# IO.net
KiCad netlist of a schematic drawn in Altium Designer
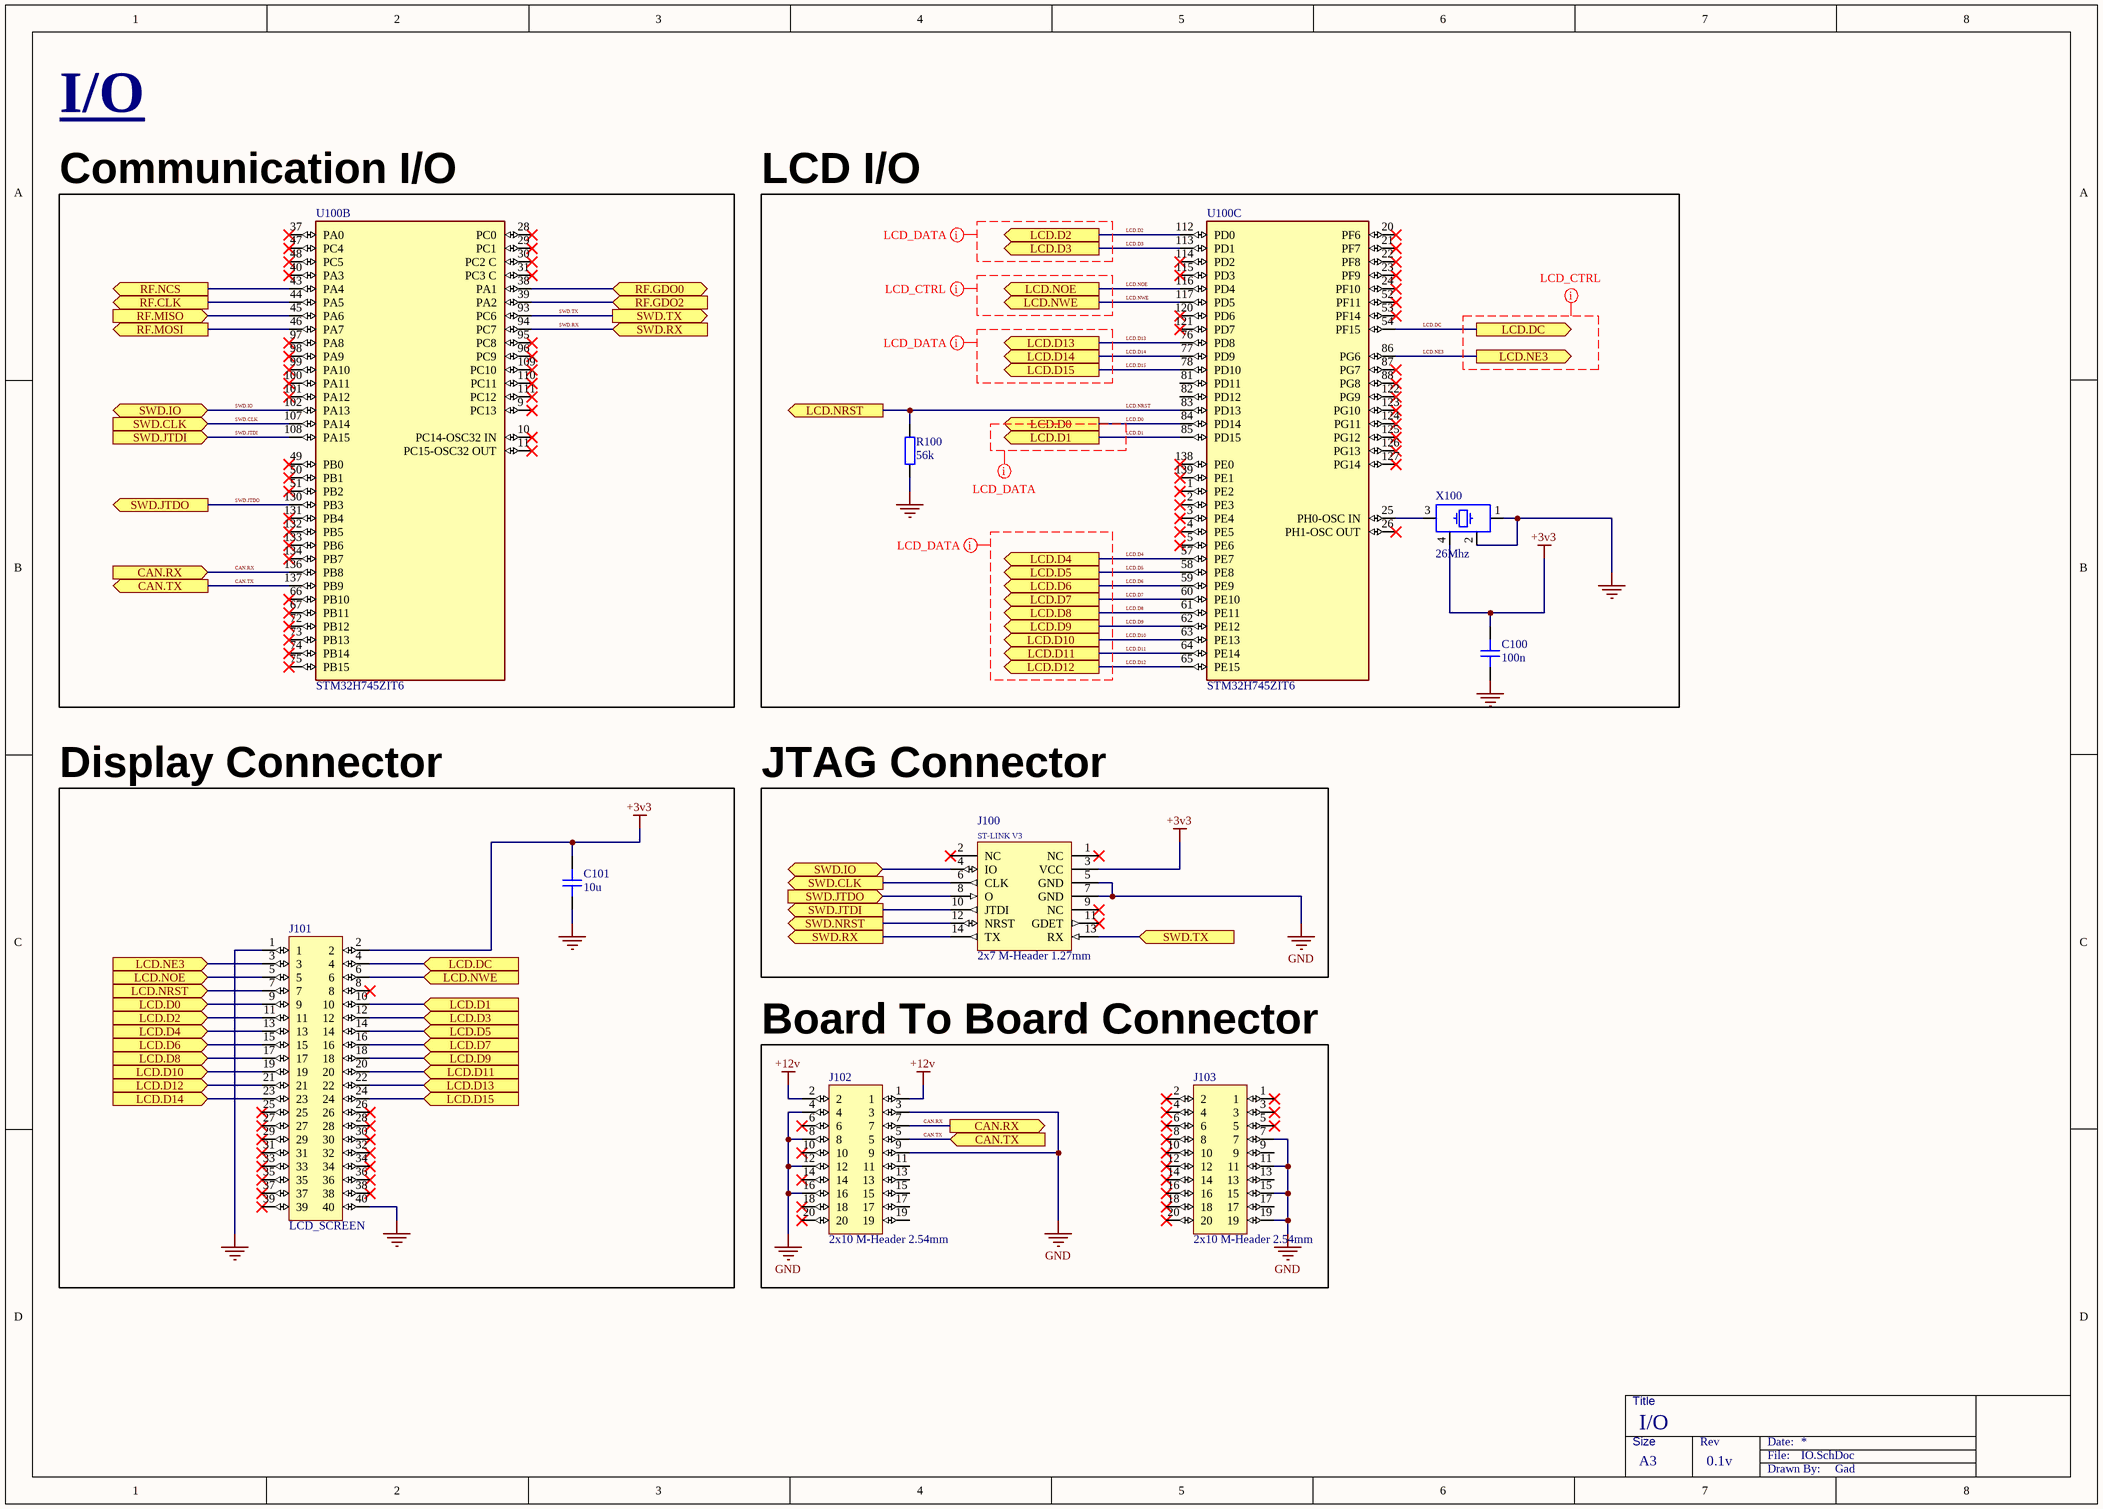
[diagram p0: IO.SchDoc]

(export (version "E")
  (design (tool "Eeschema 10.0.6"))
  (components
    (comp (ref "C100")
      (value "100n")
      (footprint "CAP_0402")
      (description "Capacitor SMD 0402 X7R 50V 10% 100nF")
      (libsource (lib "Schematic-Lib-PhilsLab") (part "CAP_0402"))
    )
    (comp (ref "C101")
      (value "10u")
      (footprint "CAP_0603")
      (description "Capacitor SMD 0603 X5R 25V 10% 10uF")
      (libsource (lib "Schematic-Lib-PhilsLab") (part "CAP_0603"))
    )
    (comp (ref "J100")
      (value "2x7 M-Header 1.27mm")
      (footprint "2x7 M-Header 1.27mm")
      (description "ST-LINK v3-minie Connector")
      (libsource (lib "Schematic-Lib-PhilsLab") (part "2x7 M-Header 1.27mm"))
    )
    (comp (ref "J101")
      (value "LCD_SCREEN")
      (footprint "LCD_Screen")
      (libsource (lib "Schematic-Lib-PhilsLab") (part "LCD_SCREEN"))
    )
    (comp (ref "J102")
      (value "2x10 M-Header 2.54mm")
      (footprint "2x10 M-Header 2.54mm")
      (libsource (lib "") (part "2x10 M-Header 2.54mm_1"))
    )
    (comp (ref "J103")
      (value "2x10 M-Header 2.54mm")
      (footprint "2x10 M-Header 2.54mm")
      (libsource (lib "Schematic-Lib-PhilsLab") (part "2x10 M-Header 2.54mm"))
    )
    (comp (ref "R100")
      (value "56k")
      (footprint "RES_0402")
      (description "Resistor SMD Thick Film 0402 75V 100mW 1% 56kΩ")
      (libsource (lib "Schematic-Lib-PhilsLab") (part "RES_0402"))
    )
    (comp (ref "U100")
      (value "STM32H745ZIT6")
      (footprint "FP-LQFP144-1A-MFG")
      (description "HIGH-PERFORMANCE AND DSP WITH DP")
      (fields
        (field (name "OCTOPART") "https://octopart.com/stm32h745zit6-stmicroelectronics-100293939")
        (field (name "MANUFACTURER") "STMicroelectronics")
      )
      (libsource (lib "Altium Content Vault") (part "f5432ce9894f79c0085309acf87c031"))
    )
    (comp (ref "X100")
      (value "26Mhz")
      (footprint "XTAL_2520")
      (description "Crystal SMD 2520")
      (fields (field (name "MANUFACTURER PART NUMBER") "OW3EL89CENUNFAYLC-26M"))
      (libsource (lib "Schematic-Lib-PhilsLab") (part "XTAL_2520"))
    )
  )
  (nets
    (net (code "1") (name "+3v3") (class "Default")
      (node (ref "C100") (pin "1") (pinfunction "1_1") (pintype "passive"))
      (node (ref "C101") (pin "1") (pinfunction "1_1") (pintype "passive"))
      (node (ref "J100") (pin "3") (pinfunction "VCC_3") (pintype "power_in"))
      (node (ref "J101") (pin "2") (pinfunction "2_2") (pintype "bidirectional"))
      (node (ref "X100") (pin "4") (pinfunction "4_4") (pintype "passive"))
    )
    (net (code "2") (name "+12v") (class "Default")
      (node (ref "J102") (pin "1") (pinfunction "1_1") (pintype "bidirectional"))
      (node (ref "J102") (pin "2") (pinfunction "2_2") (pintype "bidirectional"))
    )
    (net (code "3") (name "/CAN.RX") (class "Default")
      (node (ref "J102") (pin "7") (pinfunction "7_7") (pintype "bidirectional"))
      (node (ref "U100") (pin "136") (pinfunction "PB8_136") (pintype "bidirectional"))
    )
    (net (code "4") (name "/CAN.TX") (class "Default")
      (node (ref "J102") (pin "5") (pinfunction "5_5") (pintype "bidirectional"))
      (node (ref "U100") (pin "137") (pinfunction "PB9_137") (pintype "bidirectional"))
    )
    (net (code "5") (name "/LCD.D0") (class "Default")
      (node (ref "J101") (pin "9") (pinfunction "9_9") (pintype "bidirectional"))
      (node (ref "U100") (pin "84") (pinfunction "PD14_84") (pintype "bidirectional"))
    )
    (net (code "6") (name "/LCD.D1") (class "Default")
      (node (ref "J101") (pin "10") (pinfunction "10_10") (pintype "bidirectional"))
      (node (ref "U100") (pin "85") (pinfunction "PD15_85") (pintype "bidirectional"))
    )
    (net (code "7") (name "/LCD.D2") (class "Default")
      (node (ref "J101") (pin "11") (pinfunction "11_11") (pintype "bidirectional"))
      (node (ref "U100") (pin "112") (pinfunction "PD0_112") (pintype "bidirectional"))
    )
    (net (code "8") (name "/LCD.D3") (class "Default")
      (node (ref "J101") (pin "12") (pinfunction "12_12") (pintype "bidirectional"))
      (node (ref "U100") (pin "113") (pinfunction "PD1_113") (pintype "bidirectional"))
    )
    (net (code "9") (name "/LCD.D4") (class "Default")
      (node (ref "J101") (pin "13") (pinfunction "13_13") (pintype "bidirectional"))
      (node (ref "U100") (pin "57") (pinfunction "PE7_57") (pintype "bidirectional"))
    )
    (net (code "10") (name "/LCD.D5") (class "Default")
      (node (ref "J101") (pin "14") (pinfunction "14_14") (pintype "bidirectional"))
      (node (ref "U100") (pin "58") (pinfunction "PE8_58") (pintype "bidirectional"))
    )
    (net (code "11") (name "/LCD.D6") (class "Default")
      (node (ref "J101") (pin "15") (pinfunction "15_15") (pintype "bidirectional"))
      (node (ref "U100") (pin "59") (pinfunction "PE9_59") (pintype "bidirectional"))
    )
    (net (code "12") (name "/LCD.D7") (class "Default")
      (node (ref "J101") (pin "16") (pinfunction "16_16") (pintype "bidirectional"))
      (node (ref "U100") (pin "60") (pinfunction "PE10_60") (pintype "bidirectional"))
    )
    (net (code "13") (name "/LCD.D8") (class "Default")
      (node (ref "J101") (pin "17") (pinfunction "17_17") (pintype "bidirectional"))
      (node (ref "U100") (pin "61") (pinfunction "PE11_61") (pintype "bidirectional"))
    )
    (net (code "14") (name "/LCD.D9") (class "Default")
      (node (ref "J101") (pin "18") (pinfunction "18_18") (pintype "bidirectional"))
      (node (ref "U100") (pin "62") (pinfunction "PE12_62") (pintype "bidirectional"))
    )
    (net (code "15") (name "/LCD.D10") (class "Default")
      (node (ref "J101") (pin "19") (pinfunction "19_19") (pintype "bidirectional"))
      (node (ref "U100") (pin "63") (pinfunction "PE13_63") (pintype "bidirectional"))
    )
    (net (code "16") (name "/LCD.D11") (class "Default")
      (node (ref "J101") (pin "20") (pinfunction "20_20") (pintype "bidirectional"))
      (node (ref "U100") (pin "64") (pinfunction "PE14_64") (pintype "bidirectional"))
    )
    (net (code "17") (name "/LCD.D12") (class "Default")
      (node (ref "J101") (pin "21") (pinfunction "21_21") (pintype "bidirectional"))
      (node (ref "U100") (pin "65") (pinfunction "PE15_65") (pintype "bidirectional"))
    )
    (net (code "18") (name "/LCD.D13") (class "Default")
      (node (ref "J101") (pin "22") (pinfunction "22_22") (pintype "bidirectional"))
      (node (ref "U100") (pin "76") (pinfunction "PD8_76") (pintype "bidirectional"))
    )
    (net (code "19") (name "/LCD.D14") (class "Default")
      (node (ref "J101") (pin "23") (pinfunction "23_23") (pintype "bidirectional"))
      (node (ref "U100") (pin "77") (pinfunction "PD9_77") (pintype "bidirectional"))
    )
    (net (code "20") (name "/LCD.D15") (class "Default")
      (node (ref "J101") (pin "24") (pinfunction "24_24") (pintype "bidirectional"))
      (node (ref "U100") (pin "78") (pinfunction "PD10_78") (pintype "bidirectional"))
    )
    (net (code "21") (name "/LCD.DC") (class "Default")
      (node (ref "J101") (pin "4") (pinfunction "4_4") (pintype "bidirectional"))
      (node (ref "U100") (pin "54") (pinfunction "PF15_54") (pintype "bidirectional"))
    )
    (net (code "22") (name "/LCD.NE3") (class "Default")
      (node (ref "J101") (pin "3") (pinfunction "3_3") (pintype "bidirectional"))
      (node (ref "U100") (pin "86") (pinfunction "PG6_86") (pintype "bidirectional"))
    )
    (net (code "23") (name "/LCD.NOE") (class "Default")
      (node (ref "J101") (pin "5") (pinfunction "5_5") (pintype "bidirectional"))
      (node (ref "U100") (pin "116") (pinfunction "PD4_116") (pintype "bidirectional"))
    )
    (net (code "24") (name "/LCD.NRST") (class "Default")
      (node (ref "J101") (pin "7") (pinfunction "7_7") (pintype "bidirectional"))
      (node (ref "R100") (pin "2") (pinfunction "2_2") (pintype "passive"))
      (node (ref "U100") (pin "83") (pinfunction "PD13_83") (pintype "bidirectional"))
    )
    (net (code "25") (name "/LCD.NWE") (class "Default")
      (node (ref "J101") (pin "6") (pinfunction "6_6") (pintype "bidirectional"))
      (node (ref "U100") (pin "117") (pinfunction "PD5_117") (pintype "bidirectional"))
    )
    (net (code "26") (name "/RF.CLK") (class "Default")
      (node (ref "U100") (pin "44") (pinfunction "PA5_44") (pintype "bidirectional"))
    )
    (net (code "27") (name "/RF.GDO0") (class "Default")
      (node (ref "U100") (pin "38") (pinfunction "PA1_38") (pintype "bidirectional"))
    )
    (net (code "28") (name "/RF.GDO2") (class "Default")
      (node (ref "U100") (pin "39") (pinfunction "PA2_39") (pintype "bidirectional"))
    )
    (net (code "29") (name "/RF.MISO") (class "Default")
      (node (ref "U100") (pin "45") (pinfunction "PA6_45") (pintype "bidirectional"))
    )
    (net (code "30") (name "/RF.MOSI") (class "Default")
      (node (ref "U100") (pin "46") (pinfunction "PA7_46") (pintype "bidirectional"))
    )
    (net (code "31") (name "/RF.NCS") (class "Default")
      (node (ref "U100") (pin "43") (pinfunction "PA4_43") (pintype "bidirectional"))
    )
    (net (code "32") (name "/SWD.CLK") (class "Default")
      (node (ref "J100") (pin "6") (pinfunction "CLK_6") (pintype "output"))
      (node (ref "U100") (pin "107") (pinfunction "PA14_107") (pintype "bidirectional"))
    )
    (net (code "33") (name "/SWD.IO") (class "Default")
      (node (ref "J100") (pin "4") (pinfunction "IO_4") (pintype "bidirectional"))
      (node (ref "U100") (pin "102") (pinfunction "PA13_102") (pintype "bidirectional"))
    )
    (net (code "34") (name "/SWD.JTDI") (class "Default")
      (node (ref "J100") (pin "10") (pinfunction "JTDI_10") (pintype "output"))
      (node (ref "U100") (pin "108") (pinfunction "PA15_108") (pintype "bidirectional"))
    )
    (net (code "35") (name "/SWD.JTDO") (class "Default")
      (node (ref "J100") (pin "8") (pinfunction "O_8") (pintype "input"))
      (node (ref "U100") (pin "130") (pinfunction "PB3_130") (pintype "bidirectional"))
    )
    (net (code "36") (name "/SWD.NRST") (class "Default")
      (node (ref "J100") (pin "12") (pinfunction "NRST_12") (pintype "bidirectional"))
    )
    (net (code "37") (name "/SWD.RX") (class "Default")
      (node (ref "J100") (pin "14") (pinfunction "TX_14") (pintype "output"))
      (node (ref "U100") (pin "94") (pinfunction "PC7_94") (pintype "bidirectional"))
    )
    (net (code "38") (name "/SWD.TX") (class "Default")
      (node (ref "J100") (pin "13") (pinfunction "RX_13") (pintype "input"))
      (node (ref "U100") (pin "93") (pinfunction "PC6_93") (pintype "bidirectional"))
    )
    (net (code "39") (name "GND") (class "Default")
      (node (ref "C100") (pin "2") (pinfunction "2_2") (pintype "passive"))
      (node (ref "C101") (pin "2") (pinfunction "2_2") (pintype "passive"))
      (node (ref "J100") (pin "5") (pinfunction "GND_5") (pintype "passive"))
      (node (ref "J100") (pin "7") (pinfunction "GND_7") (pintype "passive"))
      (node (ref "J101") (pin "1") (pinfunction "1_1") (pintype "bidirectional"))
      (node (ref "J101") (pin "40") (pinfunction "40_40") (pintype "bidirectional"))
      (node (ref "J102") (pin "12") (pinfunction "12_12") (pintype "bidirectional"))
      (node (ref "J102") (pin "16") (pinfunction "16_16") (pintype "bidirectional"))
      (node (ref "J102") (pin "3") (pinfunction "3_3") (pintype "bidirectional"))
      (node (ref "J102") (pin "4") (pinfunction "4_4") (pintype "bidirectional"))
      (node (ref "J102") (pin "8") (pinfunction "8_8") (pintype "bidirectional"))
      (node (ref "J102") (pin "9") (pinfunction "9_9") (pintype "bidirectional"))
      (node (ref "J103") (pin "11") (pinfunction "11_11") (pintype "bidirectional"))
      (node (ref "J103") (pin "15") (pinfunction "15_15") (pintype "bidirectional"))
      (node (ref "J103") (pin "19") (pinfunction "19_19") (pintype "bidirectional"))
      (node (ref "J103") (pin "7") (pinfunction "7_7") (pintype "bidirectional"))
      (node (ref "R100") (pin "1") (pinfunction "1_1") (pintype "passive"))
      (node (ref "X100") (pin "1") (pinfunction "1_1") (pintype "passive"))
      (node (ref "X100") (pin "2") (pinfunction "2_2") (pintype "passive"))
    )
    (net (code "40") (name "Net-(U100C-PH0-OSC_IN)") (class "Default")
      (node (ref "U100") (pin "25") (pinfunction "PH0-OSC_IN_25") (pintype "bidirectional"))
      (node (ref "X100") (pin "3") (pinfunction "3_3") (pintype "passive"))
    )
    (net (code "41") (name "unconnected-(J100-GDET-Pad11)") (class "Default")
      (node (ref "J100") (pin "11") (pinfunction "GDET_11") (pintype "output+no_connect"))
    )
    (net (code "42") (name "unconnected-(J100-NC-Pad1)") (class "Default")
      (node (ref "J100") (pin "1") (pinfunction "NC_1") (pintype "passive+no_connect"))
    )
    (net (code "43") (name "unconnected-(J100-NC-Pad2)") (class "Default")
      (node (ref "J100") (pin "2") (pinfunction "NC_2") (pintype "passive+no_connect"))
    )
    (net (code "44") (name "unconnected-(J100-NC-Pad9)") (class "Default")
      (node (ref "J100") (pin "9") (pinfunction "NC_9") (pintype "passive+no_connect"))
    )
    (net (code "45") (name "unconnected-(J101-Pad8)") (class "Default")
      (node (ref "J101") (pin "8") (pinfunction "8_8") (pintype "bidirectional+no_connect"))
    )
    (net (code "46") (name "unconnected-(J101-Pad25)") (class "Default")
      (node (ref "J101") (pin "25") (pinfunction "25_25") (pintype "bidirectional+no_connect"))
    )
    (net (code "47") (name "unconnected-(J101-Pad26)") (class "Default")
      (node (ref "J101") (pin "26") (pinfunction "26_26") (pintype "bidirectional+no_connect"))
    )
    (net (code "48") (name "unconnected-(J101-Pad27)") (class "Default")
      (node (ref "J101") (pin "27") (pinfunction "27_27") (pintype "bidirectional+no_connect"))
    )
    (net (code "49") (name "unconnected-(J101-Pad28)") (class "Default")
      (node (ref "J101") (pin "28") (pinfunction "28_28") (pintype "bidirectional+no_connect"))
    )
    (net (code "50") (name "unconnected-(J101-Pad29)") (class "Default")
      (node (ref "J101") (pin "29") (pinfunction "29_29") (pintype "bidirectional+no_connect"))
    )
    (net (code "51") (name "unconnected-(J101-Pad30)") (class "Default")
      (node (ref "J101") (pin "30") (pinfunction "30_30") (pintype "bidirectional+no_connect"))
    )
    (net (code "52") (name "unconnected-(J101-Pad31)") (class "Default")
      (node (ref "J101") (pin "31") (pinfunction "31_31") (pintype "bidirectional+no_connect"))
    )
    (net (code "53") (name "unconnected-(J101-Pad32)") (class "Default")
      (node (ref "J101") (pin "32") (pinfunction "32_32") (pintype "bidirectional+no_connect"))
    )
    (net (code "54") (name "unconnected-(J101-Pad33)") (class "Default")
      (node (ref "J101") (pin "33") (pinfunction "33_33") (pintype "bidirectional+no_connect"))
    )
    (net (code "55") (name "unconnected-(J101-Pad34)") (class "Default")
      (node (ref "J101") (pin "34") (pinfunction "34_34") (pintype "bidirectional+no_connect"))
    )
    (net (code "56") (name "unconnected-(J101-Pad35)") (class "Default")
      (node (ref "J101") (pin "35") (pinfunction "35_35") (pintype "bidirectional+no_connect"))
    )
    (net (code "57") (name "unconnected-(J101-Pad36)") (class "Default")
      (node (ref "J101") (pin "36") (pinfunction "36_36") (pintype "bidirectional+no_connect"))
    )
    (net (code "58") (name "unconnected-(J101-Pad37)") (class "Default")
      (node (ref "J101") (pin "37") (pinfunction "37_37") (pintype "bidirectional+no_connect"))
    )
    (net (code "59") (name "unconnected-(J101-Pad38)") (class "Default")
      (node (ref "J101") (pin "38") (pinfunction "38_38") (pintype "bidirectional+no_connect"))
    )
    (net (code "60") (name "unconnected-(J101-Pad39)") (class "Default")
      (node (ref "J101") (pin "39") (pinfunction "39_39") (pintype "bidirectional+no_connect"))
    )
    (net (code "61") (name "unconnected-(J102-Pad6)") (class "Default")
      (node (ref "J102") (pin "6") (pinfunction "6_6") (pintype "bidirectional+no_connect"))
    )
    (net (code "62") (name "unconnected-(J102-Pad10)") (class "Default")
      (node (ref "J102") (pin "10") (pinfunction "10_10") (pintype "bidirectional+no_connect"))
    )
    (net (code "63") (name "unconnected-(J102-Pad11)") (class "Default")
      (node (ref "J102") (pin "11") (pinfunction "11_11") (pintype "bidirectional"))
    )
    (net (code "64") (name "unconnected-(J102-Pad13)") (class "Default")
      (node (ref "J102") (pin "13") (pinfunction "13_13") (pintype "bidirectional"))
    )
    (net (code "65") (name "unconnected-(J102-Pad14)") (class "Default")
      (node (ref "J102") (pin "14") (pinfunction "14_14") (pintype "bidirectional+no_connect"))
    )
    (net (code "66") (name "unconnected-(J102-Pad15)") (class "Default")
      (node (ref "J102") (pin "15") (pinfunction "15_15") (pintype "bidirectional"))
    )
    (net (code "67") (name "unconnected-(J102-Pad17)") (class "Default")
      (node (ref "J102") (pin "17") (pinfunction "17_17") (pintype "bidirectional"))
    )
    (net (code "68") (name "unconnected-(J102-Pad18)") (class "Default")
      (node (ref "J102") (pin "18") (pinfunction "18_18") (pintype "bidirectional+no_connect"))
    )
    (net (code "69") (name "unconnected-(J102-Pad19)") (class "Default")
      (node (ref "J102") (pin "19") (pinfunction "19_19") (pintype "bidirectional"))
    )
    (net (code "70") (name "unconnected-(J102-Pad20)") (class "Default")
      (node (ref "J102") (pin "20") (pinfunction "20_20") (pintype "bidirectional+no_connect"))
    )
    (net (code "71") (name "unconnected-(J103-Pad1)") (class "Default")
      (node (ref "J103") (pin "1") (pinfunction "1_1") (pintype "bidirectional+no_connect"))
    )
    (net (code "72") (name "unconnected-(J103-Pad2)") (class "Default")
      (node (ref "J103") (pin "2") (pinfunction "2_2") (pintype "bidirectional+no_connect"))
    )
    (net (code "73") (name "unconnected-(J103-Pad3)") (class "Default")
      (node (ref "J103") (pin "3") (pinfunction "3_3") (pintype "bidirectional+no_connect"))
    )
    (net (code "74") (name "unconnected-(J103-Pad4)") (class "Default")
      (node (ref "J103") (pin "4") (pinfunction "4_4") (pintype "bidirectional+no_connect"))
    )
    (net (code "75") (name "unconnected-(J103-Pad5)") (class "Default")
      (node (ref "J103") (pin "5") (pinfunction "5_5") (pintype "bidirectional+no_connect"))
    )
    (net (code "76") (name "unconnected-(J103-Pad6)") (class "Default")
      (node (ref "J103") (pin "6") (pinfunction "6_6") (pintype "bidirectional+no_connect"))
    )
    (net (code "77") (name "unconnected-(J103-Pad8)") (class "Default")
      (node (ref "J103") (pin "8") (pinfunction "8_8") (pintype "bidirectional+no_connect"))
    )
    (net (code "78") (name "unconnected-(J103-Pad9)") (class "Default")
      (node (ref "J103") (pin "9") (pinfunction "9_9") (pintype "bidirectional"))
    )
    (net (code "79") (name "unconnected-(J103-Pad10)") (class "Default")
      (node (ref "J103") (pin "10") (pinfunction "10_10") (pintype "bidirectional+no_connect"))
    )
    (net (code "80") (name "unconnected-(J103-Pad12)") (class "Default")
      (node (ref "J103") (pin "12") (pinfunction "12_12") (pintype "bidirectional+no_connect"))
    )
    (net (code "81") (name "unconnected-(J103-Pad13)") (class "Default")
      (node (ref "J103") (pin "13") (pinfunction "13_13") (pintype "bidirectional"))
    )
    (net (code "82") (name "unconnected-(J103-Pad14)") (class "Default")
      (node (ref "J103") (pin "14") (pinfunction "14_14") (pintype "bidirectional+no_connect"))
    )
    (net (code "83") (name "unconnected-(J103-Pad16)") (class "Default")
      (node (ref "J103") (pin "16") (pinfunction "16_16") (pintype "bidirectional+no_connect"))
    )
    (net (code "84") (name "unconnected-(J103-Pad17)") (class "Default")
      (node (ref "J103") (pin "17") (pinfunction "17_17") (pintype "bidirectional"))
    )
    (net (code "85") (name "unconnected-(J103-Pad18)") (class "Default")
      (node (ref "J103") (pin "18") (pinfunction "18_18") (pintype "bidirectional+no_connect"))
    )
    (net (code "86") (name "unconnected-(J103-Pad20)") (class "Default")
      (node (ref "J103") (pin "20") (pinfunction "20_20") (pintype "bidirectional+no_connect"))
    )
    (net (code "87") (name "unconnected-(U100B-PA0-Pad37)") (class "Default")
      (node (ref "U100") (pin "37") (pinfunction "PA0_37") (pintype "bidirectional+no_connect"))
    )
    (net (code "88") (name "unconnected-(U100B-PA3-Pad40)") (class "Default")
      (node (ref "U100") (pin "40") (pinfunction "PA3_40") (pintype "bidirectional+no_connect"))
    )
    (net (code "89") (name "unconnected-(U100B-PA8-Pad97)") (class "Default")
      (node (ref "U100") (pin "97") (pinfunction "PA8_97") (pintype "bidirectional+no_connect"))
    )
    (net (code "90") (name "unconnected-(U100B-PA9-Pad98)") (class "Default")
      (node (ref "U100") (pin "98") (pinfunction "PA9_98") (pintype "bidirectional+no_connect"))
    )
    (net (code "91") (name "unconnected-(U100B-PA10-Pad99)") (class "Default")
      (node (ref "U100") (pin "99") (pinfunction "PA10_99") (pintype "bidirectional+no_connect"))
    )
    (net (code "92") (name "unconnected-(U100B-PA11-Pad100)") (class "Default")
      (node (ref "U100") (pin "100") (pinfunction "PA11_100") (pintype "bidirectional+no_connect"))
    )
    (net (code "93") (name "unconnected-(U100B-PA12-Pad101)") (class "Default")
      (node (ref "U100") (pin "101") (pinfunction "PA12_101") (pintype "bidirectional+no_connect"))
    )
    (net (code "94") (name "unconnected-(U100B-PB0-Pad49)") (class "Default")
      (node (ref "U100") (pin "49") (pinfunction "PB0_49") (pintype "bidirectional+no_connect"))
    )
    (net (code "95") (name "unconnected-(U100B-PB1-Pad50)") (class "Default")
      (node (ref "U100") (pin "50") (pinfunction "PB1_50") (pintype "bidirectional+no_connect"))
    )
    (net (code "96") (name "unconnected-(U100B-PB2-Pad51)") (class "Default")
      (node (ref "U100") (pin "51") (pinfunction "PB2_51") (pintype "bidirectional+no_connect"))
    )
    (net (code "97") (name "unconnected-(U100B-PB4-Pad131)") (class "Default")
      (node (ref "U100") (pin "131") (pinfunction "PB4_131") (pintype "bidirectional+no_connect"))
    )
    (net (code "98") (name "unconnected-(U100B-PB5-Pad132)") (class "Default")
      (node (ref "U100") (pin "132") (pinfunction "PB5_132") (pintype "bidirectional+no_connect"))
    )
    (net (code "99") (name "unconnected-(U100B-PB6-Pad133)") (class "Default")
      (node (ref "U100") (pin "133") (pinfunction "PB6_133") (pintype "bidirectional+no_connect"))
    )
    (net (code "100") (name "unconnected-(U100B-PB7-Pad134)") (class "Default")
      (node (ref "U100") (pin "134") (pinfunction "PB7_134") (pintype "bidirectional+no_connect"))
    )
    (net (code "101") (name "unconnected-(U100B-PB10-Pad66)") (class "Default")
      (node (ref "U100") (pin "66") (pinfunction "PB10_66") (pintype "bidirectional+no_connect"))
    )
    (net (code "102") (name "unconnected-(U100B-PB11-Pad67)") (class "Default")
      (node (ref "U100") (pin "67") (pinfunction "PB11_67") (pintype "bidirectional+no_connect"))
    )
    (net (code "103") (name "unconnected-(U100B-PB12-Pad72)") (class "Default")
      (node (ref "U100") (pin "72") (pinfunction "PB12_72") (pintype "bidirectional+no_connect"))
    )
    (net (code "104") (name "unconnected-(U100B-PB13-Pad73)") (class "Default")
      (node (ref "U100") (pin "73") (pinfunction "PB13_73") (pintype "bidirectional+no_connect"))
    )
    (net (code "105") (name "unconnected-(U100B-PB14-Pad74)") (class "Default")
      (node (ref "U100") (pin "74") (pinfunction "PB14_74") (pintype "bidirectional+no_connect"))
    )
    (net (code "106") (name "unconnected-(U100B-PB15-Pad75)") (class "Default")
      (node (ref "U100") (pin "75") (pinfunction "PB15_75") (pintype "bidirectional+no_connect"))
    )
    (net (code "107") (name "unconnected-(U100B-PC0-Pad28)") (class "Default")
      (node (ref "U100") (pin "28") (pinfunction "PC0_28") (pintype "bidirectional+no_connect"))
    )
    (net (code "108") (name "unconnected-(U100B-PC1-Pad29)") (class "Default")
      (node (ref "U100") (pin "29") (pinfunction "PC1_29") (pintype "bidirectional+no_connect"))
    )
    (net (code "109") (name "unconnected-(U100B-PC2_C-Pad30)") (class "Default")
      (node (ref "U100") (pin "30") (pinfunction "PC2_C_30") (pintype "bidirectional+no_connect"))
    )
    (net (code "110") (name "unconnected-(U100B-PC3_C-Pad31)") (class "Default")
      (node (ref "U100") (pin "31") (pinfunction "PC3_C_31") (pintype "bidirectional+no_connect"))
    )
    (net (code "111") (name "unconnected-(U100B-PC4-Pad47)") (class "Default")
      (node (ref "U100") (pin "47") (pinfunction "PC4_47") (pintype "bidirectional+no_connect"))
    )
    (net (code "112") (name "unconnected-(U100B-PC5-Pad48)") (class "Default")
      (node (ref "U100") (pin "48") (pinfunction "PC5_48") (pintype "bidirectional+no_connect"))
    )
    (net (code "113") (name "unconnected-(U100B-PC8-Pad95)") (class "Default")
      (node (ref "U100") (pin "95") (pinfunction "PC8_95") (pintype "bidirectional+no_connect"))
    )
    (net (code "114") (name "unconnected-(U100B-PC9-Pad96)") (class "Default")
      (node (ref "U100") (pin "96") (pinfunction "PC9_96") (pintype "bidirectional+no_connect"))
    )
    (net (code "115") (name "unconnected-(U100B-PC10-Pad109)") (class "Default")
      (node (ref "U100") (pin "109") (pinfunction "PC10_109") (pintype "bidirectional+no_connect"))
    )
    (net (code "116") (name "unconnected-(U100B-PC11-Pad110)") (class "Default")
      (node (ref "U100") (pin "110") (pinfunction "PC11_110") (pintype "bidirectional+no_connect"))
    )
    (net (code "117") (name "unconnected-(U100B-PC12-Pad111)") (class "Default")
      (node (ref "U100") (pin "111") (pinfunction "PC12_111") (pintype "bidirectional+no_connect"))
    )
    (net (code "118") (name "unconnected-(U100B-PC13-Pad9)") (class "Default")
      (node (ref "U100") (pin "9") (pinfunction "PC13_9") (pintype "bidirectional+no_connect"))
    )
    (net (code "119") (name "unconnected-(U100B-PC14-OSC32_IN-Pad10)") (class "Default")
      (node (ref "U100") (pin "10") (pinfunction "PC14-OSC32_IN_10") (pintype "bidirectional+no_connect"))
    )
    (net (code "120") (name "unconnected-(U100B-PC15-OSC32_OUT-Pad11)") (class "Default")
      (node (ref "U100") (pin "11") (pinfunction "PC15-OSC32_OUT_11") (pintype "bidirectional+no_connect"))
    )
    (net (code "121") (name "unconnected-(U100C-PD2-Pad114)") (class "Default")
      (node (ref "U100") (pin "114") (pinfunction "PD2_114") (pintype "bidirectional+no_connect"))
    )
    (net (code "122") (name "unconnected-(U100C-PD3-Pad115)") (class "Default")
      (node (ref "U100") (pin "115") (pinfunction "PD3_115") (pintype "bidirectional+no_connect"))
    )
    (net (code "123") (name "unconnected-(U100C-PD6-Pad120)") (class "Default")
      (node (ref "U100") (pin "120") (pinfunction "PD6_120") (pintype "bidirectional+no_connect"))
    )
    (net (code "124") (name "unconnected-(U100C-PD7-Pad121)") (class "Default")
      (node (ref "U100") (pin "121") (pinfunction "PD7_121") (pintype "bidirectional+no_connect"))
    )
    (net (code "125") (name "unconnected-(U100C-PD11-Pad81)") (class "Default")
      (node (ref "U100") (pin "81") (pinfunction "PD11_81") (pintype "bidirectional"))
    )
    (net (code "126") (name "unconnected-(U100C-PD12-Pad82)") (class "Default")
      (node (ref "U100") (pin "82") (pinfunction "PD12_82") (pintype "bidirectional"))
    )
    (net (code "127") (name "unconnected-(U100C-PE0-Pad138)") (class "Default")
      (node (ref "U100") (pin "138") (pinfunction "PE0_138") (pintype "bidirectional+no_connect"))
    )
    (net (code "128") (name "unconnected-(U100C-PE1-Pad139)") (class "Default")
      (node (ref "U100") (pin "139") (pinfunction "PE1_139") (pintype "bidirectional+no_connect"))
    )
    (net (code "129") (name "unconnected-(U100C-PE2-Pad1)") (class "Default")
      (node (ref "U100") (pin "1") (pinfunction "PE2_1") (pintype "bidirectional+no_connect"))
    )
    (net (code "130") (name "unconnected-(U100C-PE3-Pad2)") (class "Default")
      (node (ref "U100") (pin "2") (pinfunction "PE3_2") (pintype "bidirectional+no_connect"))
    )
    (net (code "131") (name "unconnected-(U100C-PE4-Pad3)") (class "Default")
      (node (ref "U100") (pin "3") (pinfunction "PE4_3") (pintype "bidirectional+no_connect"))
    )
    (net (code "132") (name "unconnected-(U100C-PE5-Pad4)") (class "Default")
      (node (ref "U100") (pin "4") (pinfunction "PE5_4") (pintype "bidirectional+no_connect"))
    )
    (net (code "133") (name "unconnected-(U100C-PE6-Pad5)") (class "Default")
      (node (ref "U100") (pin "5") (pinfunction "PE6_5") (pintype "bidirectional+no_connect"))
    )
    (net (code "134") (name "unconnected-(U100C-PF6-Pad20)") (class "Default")
      (node (ref "U100") (pin "20") (pinfunction "PF6_20") (pintype "bidirectional+no_connect"))
    )
    (net (code "135") (name "unconnected-(U100C-PF7-Pad21)") (class "Default")
      (node (ref "U100") (pin "21") (pinfunction "PF7_21") (pintype "bidirectional+no_connect"))
    )
    (net (code "136") (name "unconnected-(U100C-PF8-Pad22)") (class "Default")
      (node (ref "U100") (pin "22") (pinfunction "PF8_22") (pintype "bidirectional+no_connect"))
    )
    (net (code "137") (name "unconnected-(U100C-PF9-Pad23)") (class "Default")
      (node (ref "U100") (pin "23") (pinfunction "PF9_23") (pintype "bidirectional+no_connect"))
    )
    (net (code "138") (name "unconnected-(U100C-PF10-Pad24)") (class "Default")
      (node (ref "U100") (pin "24") (pinfunction "PF10_24") (pintype "bidirectional+no_connect"))
    )
    (net (code "139") (name "unconnected-(U100C-PF11-Pad52)") (class "Default")
      (node (ref "U100") (pin "52") (pinfunction "PF11_52") (pintype "bidirectional+no_connect"))
    )
    (net (code "140") (name "unconnected-(U100C-PF14-Pad53)") (class "Default")
      (node (ref "U100") (pin "53") (pinfunction "PF14_53") (pintype "bidirectional+no_connect"))
    )
    (net (code "141") (name "unconnected-(U100C-PG7-Pad87)") (class "Default")
      (node (ref "U100") (pin "87") (pinfunction "PG7_87") (pintype "bidirectional+no_connect"))
    )
    (net (code "142") (name "unconnected-(U100C-PG8-Pad88)") (class "Default")
      (node (ref "U100") (pin "88") (pinfunction "PG8_88") (pintype "bidirectional+no_connect"))
    )
    (net (code "143") (name "unconnected-(U100C-PG9-Pad122)") (class "Default")
      (node (ref "U100") (pin "122") (pinfunction "PG9_122") (pintype "bidirectional+no_connect"))
    )
    (net (code "144") (name "unconnected-(U100C-PG10-Pad123)") (class "Default")
      (node (ref "U100") (pin "123") (pinfunction "PG10_123") (pintype "bidirectional+no_connect"))
    )
    (net (code "145") (name "unconnected-(U100C-PG11-Pad124)") (class "Default")
      (node (ref "U100") (pin "124") (pinfunction "PG11_124") (pintype "bidirectional+no_connect"))
    )
    (net (code "146") (name "unconnected-(U100C-PG12-Pad125)") (class "Default")
      (node (ref "U100") (pin "125") (pinfunction "PG12_125") (pintype "bidirectional+no_connect"))
    )
    (net (code "147") (name "unconnected-(U100C-PG13-Pad126)") (class "Default")
      (node (ref "U100") (pin "126") (pinfunction "PG13_126") (pintype "bidirectional+no_connect"))
    )
    (net (code "148") (name "unconnected-(U100C-PG14-Pad127)") (class "Default")
      (node (ref "U100") (pin "127") (pinfunction "PG14_127") (pintype "bidirectional+no_connect"))
    )
    (net (code "149") (name "unconnected-(U100C-PH1-OSC_OUT-Pad26)") (class "Default")
      (node (ref "U100") (pin "26") (pinfunction "PH1-OSC_OUT_26") (pintype "bidirectional+no_connect"))
    )
  )
)
